# LCDTFT_FPC40P_SPI3_3p5INCH_RTP.net
KiCad netlist of a schematic drawn in Altium Designer
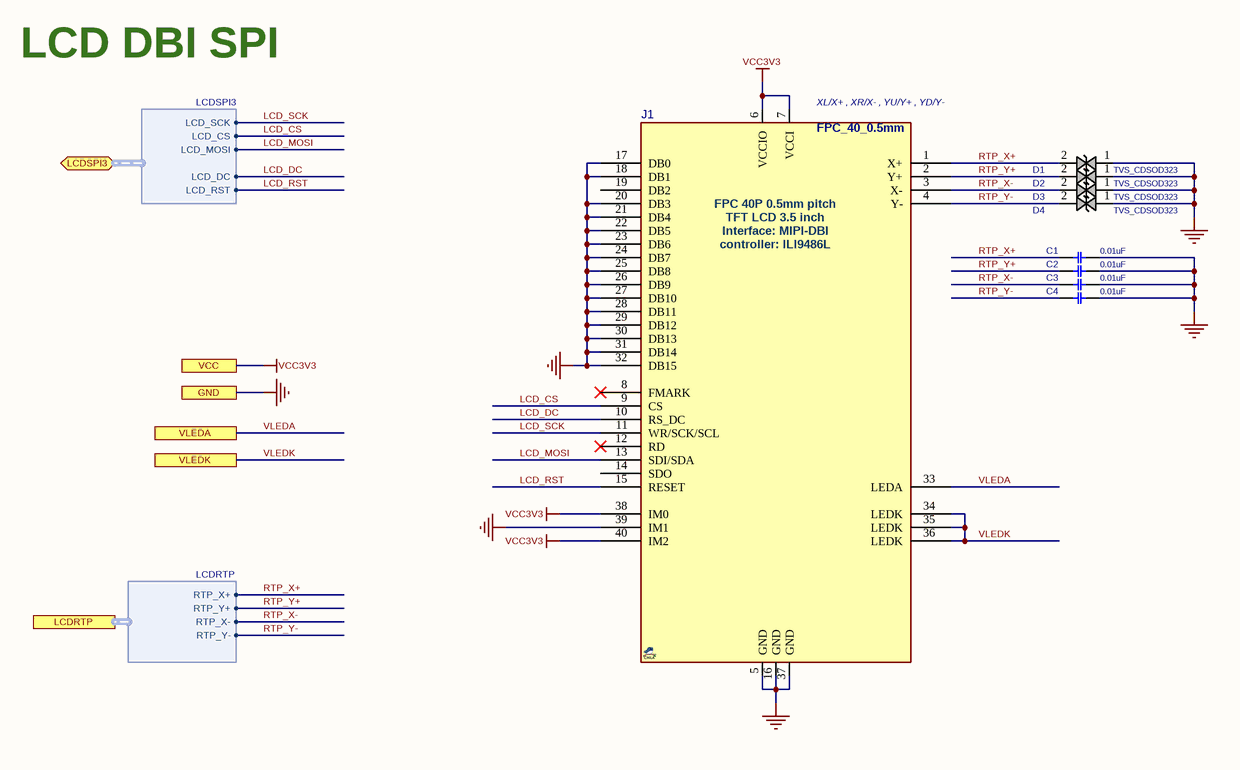
[diagram p0: LCDTFT_FPC40P_SPI3_3p5INCH_RTP.SchDoc]

(export (version "E")
  (design (tool "Eeschema 10.0.6"))
  (components
    (comp (ref "C1")
      (value "0.01uF")
      (footprint "C0402")
      (description "CAP, MLCC")
      (libsource (lib "passive_smd") (part "CAP_SMD_MLCC"))
    )
    (comp (ref "C2")
      (value "0.01uF")
      (footprint "C0402")
      (description "CAP, MLCC")
      (libsource (lib "passive_smd") (part "CAP_SMD_MLCC"))
    )
    (comp (ref "C3")
      (value "0.01uF")
      (footprint "C0402")
      (description "CAP, MLCC")
      (libsource (lib "passive_smd") (part "CAP_SMD_MLCC"))
    )
    (comp (ref "C4")
      (value "0.01uF")
      (footprint "C0402")
      (description "CAP, MLCC")
      (libsource (lib "passive_smd") (part "CAP_SMD_MLCC"))
    )
    (comp (ref "D1")
      (value "TVS_CDSOD323")
      (footprint "D0805")
      (description "TVS, ESD PROTECT, Bidirectional")
      (fields (field (name "MANF_P#") "CDSOD323-T12C") (field (name "MANF") "Bourns"))
      (libsource (lib "protect_tvs_esd_fuse") (part "TVS_CDSOD323"))
    )
    (comp (ref "D2")
      (value "TVS_CDSOD323")
      (footprint "D0805")
      (description "TVS, ESD PROTECT, Bidirectional")
      (fields (field (name "MANF_P#") "CDSOD323-T12C") (field (name "MANF") "Bourns"))
      (libsource (lib "protect_tvs_esd_fuse") (part "TVS_CDSOD323"))
    )
    (comp (ref "D3")
      (value "TVS_CDSOD323")
      (footprint "D0805")
      (description "TVS, ESD PROTECT, Bidirectional")
      (fields (field (name "MANF_P#") "CDSOD323-T12C") (field (name "MANF") "Bourns"))
      (libsource (lib "protect_tvs_esd_fuse") (part "TVS_CDSOD323"))
    )
    (comp (ref "D4")
      (value "TVS_CDSOD323")
      (footprint "D0805")
      (description "TVS, ESD PROTECT, Bidirectional")
      (fields (field (name "MANF_P#") "CDSOD323-T12C") (field (name "MANF") "Bourns"))
      (libsource (lib "protect_tvs_esd_fuse") (part "TVS_CDSOD323"))
    )
    (comp (ref "J1")
      (value "FPC50_40")
      (footprint "FPC50_40T")
      (description "LCD TFT Color, FPC40P, 3.5\" with touch")
      (fields (field (name "MANF") "Hirose") (field (name "MANF_P#") "FH12A-40S-0.5SH"))
      (libsource (lib "lcdtft") (part "LCDTFT_DBI_FPC40P_3.5INCH"))
    )
  )
  (nets
    (net (code "3") (name "/LCD_CS") (class "Default")
      (node (ref "J1") (pin "9") (pinfunction "CS_9") (pintype "passive"))
    )
    (net (code "4") (name "/LCD_DC") (class "Default")
      (node (ref "J1") (pin "10") (pinfunction "RS_DC_10") (pintype "passive"))
    )
    (net (code "5") (name "/LCD_MOSI") (class "Default")
      (node (ref "J1") (pin "13") (pinfunction "SDI/SDA_13") (pintype "passive"))
    )
    (net (code "6") (name "/LCD_RST") (class "Default")
      (node (ref "J1") (pin "15") (pinfunction "RESET_15") (pintype "passive"))
    )
    (net (code "7") (name "/LCD_SCK") (class "Default")
      (node (ref "J1") (pin "11") (pinfunction "WR/SCK/SCL_11") (pintype "passive"))
    )
    (net (code "8") (name "/RTP_X+") (class "Default")
      (node (ref "C1") (pin "2") (pinfunction "2_2") (pintype "passive"))
      (node (ref "D1") (pin "2") (pinfunction "2_2") (pintype "passive"))
      (node (ref "J1") (pin "1") (pinfunction "X+_1") (pintype "passive"))
    )
    (net (code "9") (name "/RTP_X-") (class "Default")
      (node (ref "C3") (pin "2") (pinfunction "2_2") (pintype "passive"))
      (node (ref "D3") (pin "2") (pinfunction "2_2") (pintype "passive"))
      (node (ref "J1") (pin "3") (pinfunction "X-_3") (pintype "passive"))
    )
    (net (code "10") (name "/RTP_Y+") (class "Default")
      (node (ref "C2") (pin "2") (pinfunction "2_2") (pintype "passive"))
      (node (ref "D2") (pin "2") (pinfunction "2_2") (pintype "passive"))
      (node (ref "J1") (pin "2") (pinfunction "Y+_2") (pintype "passive"))
    )
    (net (code "11") (name "/RTP_Y-") (class "Default")
      (node (ref "C4") (pin "2") (pinfunction "2_2") (pintype "passive"))
      (node (ref "D4") (pin "2") (pinfunction "2_2") (pintype "passive"))
      (node (ref "J1") (pin "4") (pinfunction "Y-_4") (pintype "passive"))
    )
    (net (code "12") (name "/VLEDA") (class "Default")
      (node (ref "J1") (pin "33") (pinfunction "LEDA_33") (pintype "passive"))
    )
    (net (code "13") (name "/VLEDK") (class "Default")
      (node (ref "J1") (pin "34") (pinfunction "LEDK_34") (pintype "passive"))
      (node (ref "J1") (pin "35") (pinfunction "LEDK_35") (pintype "passive"))
      (node (ref "J1") (pin "36") (pinfunction "LEDK_36") (pintype "passive"))
    )
    (net (code "16") (name "GND") (class "Default")
      (node (ref "C1") (pin "1") (pinfunction "1_1") (pintype "passive"))
      (node (ref "C2") (pin "1") (pinfunction "1_1") (pintype "passive"))
      (node (ref "C3") (pin "1") (pinfunction "1_1") (pintype "passive"))
      (node (ref "C4") (pin "1") (pinfunction "1_1") (pintype "passive"))
      (node (ref "D1") (pin "1") (pinfunction "1_1") (pintype "passive"))
      (node (ref "D2") (pin "1") (pinfunction "1_1") (pintype "passive"))
      (node (ref "D3") (pin "1") (pinfunction "1_1") (pintype "passive"))
      (node (ref "D4") (pin "1") (pinfunction "1_1") (pintype "passive"))
      (node (ref "J1") (pin "16") (pinfunction "GND_16") (pintype "passive"))
      (node (ref "J1") (pin "17") (pinfunction "DB0_17") (pintype "passive"))
      (node (ref "J1") (pin "18") (pinfunction "DB1_18") (pintype "passive"))
      (node (ref "J1") (pin "20") (pinfunction "DB3_20") (pintype "passive"))
      (node (ref "J1") (pin "21") (pinfunction "DB4_21") (pintype "passive"))
      (node (ref "J1") (pin "22") (pinfunction "DB5_22") (pintype "passive"))
      (node (ref "J1") (pin "23") (pinfunction "DB6_23") (pintype "passive"))
      (node (ref "J1") (pin "24") (pinfunction "DB7_24") (pintype "passive"))
      (node (ref "J1") (pin "25") (pinfunction "DB8_25") (pintype "passive"))
      (node (ref "J1") (pin "26") (pinfunction "DB9_26") (pintype "passive"))
      (node (ref "J1") (pin "27") (pinfunction "DB10_27") (pintype "passive"))
      (node (ref "J1") (pin "28") (pinfunction "DB11_28") (pintype "passive"))
      (node (ref "J1") (pin "29") (pinfunction "DB12_29") (pintype "passive"))
      (node (ref "J1") (pin "30") (pinfunction "DB13_30") (pintype "passive"))
      (node (ref "J1") (pin "31") (pinfunction "DB14_31") (pintype "passive"))
      (node (ref "J1") (pin "32") (pinfunction "DB15_32") (pintype "passive"))
      (node (ref "J1") (pin "37") (pinfunction "GND_37") (pintype "passive"))
      (node (ref "J1") (pin "39") (pinfunction "IM1_39") (pintype "passive"))
      (node (ref "J1") (pin "5") (pinfunction "GND_5") (pintype "passive"))
    )
    (net (code "17") (name "VCC3V3") (class "Default")
      (node (ref "J1") (pin "38") (pinfunction "IM0_38") (pintype "passive"))
      (node (ref "J1") (pin "40") (pinfunction "IM2_40") (pintype "passive"))
      (node (ref "J1") (pin "6") (pinfunction "VCCIO_6") (pintype "passive"))
      (node (ref "J1") (pin "7") (pinfunction "VCCI_7") (pintype "passive"))
    )
    (net (code "18") (name "unconnected-(J1-DB2-Pad19)") (class "Default")
      (node (ref "J1") (pin "19") (pinfunction "DB2_19") (pintype "passive"))
    )
    (net (code "19") (name "unconnected-(J1-FMARK-Pad8)") (class "Default")
      (node (ref "J1") (pin "8") (pinfunction "FMARK_8") (pintype "passive+no_connect"))
    )
    (net (code "20") (name "unconnected-(J1-RD-Pad12)") (class "Default")
      (node (ref "J1") (pin "12") (pinfunction "RD_12") (pintype "passive+no_connect"))
    )
    (net (code "21") (name "unconnected-(J1-SDO-Pad14)") (class "Default")
      (node (ref "J1") (pin "14") (pinfunction "SDO_14") (pintype "passive"))
    )
  )
)
